# adapter.net
KiCad netlist of a schematic drawn in EAGLE
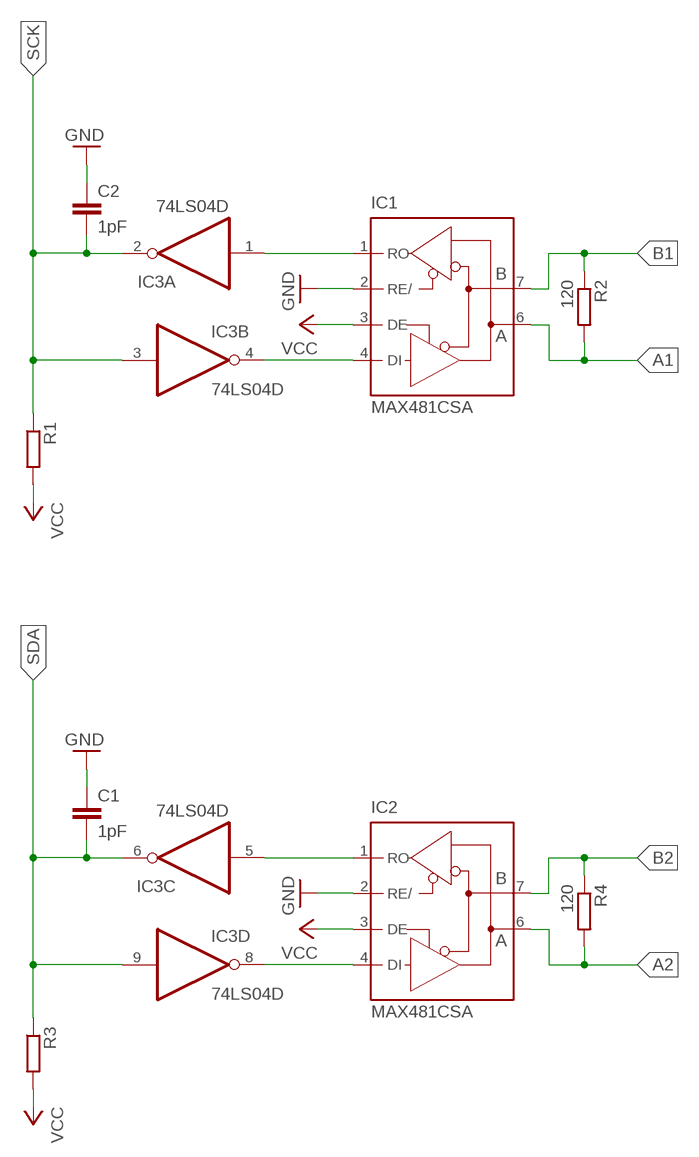
[diagram p0: schematic, sheet 1]

(export (version "E")
  (design (tool "Eeschema 10.0.6"))
  (components
    (comp (ref "C1")
      (value "1pF")
      (footprint "eagle-import:C0805")
      (libsource (lib "eagle-import") (part "C"))
    )
    (comp (ref "C2")
      (value "1pF")
      (footprint "eagle-import:C0805")
      (libsource (lib "eagle-import") (part "C"))
    )
    (comp (ref "IC1")
      (value "MAX481CSA")
      (footprint "eagle-import:SO08")
      (libsource (lib "eagle-import") (part "MAX481CSA"))
    )
    (comp (ref "IC2")
      (value "MAX481CSA")
      (footprint "eagle-import:SO08")
      (libsource (lib "eagle-import") (part "MAX481CSA"))
    )
    (comp (ref "IC3")
      (value "74LS04D")
      (footprint "eagle-import:SO14")
      (libsource (lib "eagle-import") (part "7404DLS"))
    )
    (comp (ref "R1")
      (value "R0204/7")
      (footprint "eagle-import:0204_7")
      (libsource (lib "eagle-import") (part "R0204/7"))
    )
    (comp (ref "R2")
      (value "120")
      (footprint "eagle-import:0204_7")
      (libsource (lib "eagle-import") (part "R0204/7"))
    )
    (comp (ref "R3")
      (value "R0204/7")
      (footprint "eagle-import:0204_7")
      (libsource (lib "eagle-import") (part "R0204/7"))
    )
    (comp (ref "R4")
      (value "120")
      (footprint "eagle-import:0204_7")
      (libsource (lib "eagle-import") (part "R0204/7"))
    )
  )
  (nets
    (net (code "1") (name "A1") (class "Default")
      (node (ref "IC1") (pin "6") (pinfunction "A_6") (pintype "passive"))
      (node (ref "R2") (pin "2") (pinfunction "2_2") (pintype "passive"))
    )
    (net (code "2") (name "A2") (class "Default")
      (node (ref "IC2") (pin "6") (pinfunction "A_6") (pintype "passive"))
      (node (ref "R4") (pin "2") (pinfunction "2_2") (pintype "passive"))
    )
    (net (code "3") (name "B1") (class "Default")
      (node (ref "IC1") (pin "7") (pinfunction "B_7") (pintype "passive"))
      (node (ref "R2") (pin "1") (pinfunction "1_1") (pintype "passive"))
    )
    (net (code "4") (name "B2") (class "Default")
      (node (ref "IC2") (pin "7") (pinfunction "B_7") (pintype "passive"))
      (node (ref "R4") (pin "1") (pinfunction "1_1") (pintype "passive"))
    )
    (net (code "5") (name "GND") (class "Default")
      (node (ref "C1") (pin "1") (pinfunction "1_1") (pintype "passive"))
      (node (ref "C2") (pin "1") (pinfunction "1_1") (pintype "passive"))
      (node (ref "IC1") (pin "2") (pinfunction "RE/_2") (pintype "input"))
      (node (ref "IC2") (pin "2") (pinfunction "RE/_2") (pintype "input"))
    )
    (net (code "6") (name "Net-(IC1A-DI)") (class "Default")
      (node (ref "IC1") (pin "4") (pinfunction "DI_4") (pintype "input"))
      (node (ref "IC3") (pin "4") (pinfunction "O_4") (pintype "output"))
    )
    (net (code "7") (name "Net-(IC1A-RO)") (class "Default")
      (node (ref "IC1") (pin "1") (pinfunction "RO_1") (pintype "output"))
      (node (ref "IC3") (pin "1") (pinfunction "I_1") (pintype "input"))
    )
    (net (code "8") (name "Net-(IC2A-DI)") (class "Default")
      (node (ref "IC2") (pin "4") (pinfunction "DI_4") (pintype "input"))
      (node (ref "IC3") (pin "8") (pinfunction "O_8") (pintype "output"))
    )
    (net (code "9") (name "Net-(IC2A-RO)") (class "Default")
      (node (ref "IC2") (pin "1") (pinfunction "RO_1") (pintype "output"))
      (node (ref "IC3") (pin "5") (pinfunction "I_5") (pintype "input"))
    )
    (net (code "10") (name "SCK") (class "Default")
      (node (ref "C2") (pin "2") (pinfunction "2_2") (pintype "passive"))
      (node (ref "IC3") (pin "2") (pinfunction "O_2") (pintype "output"))
      (node (ref "IC3") (pin "3") (pinfunction "I_3") (pintype "input"))
      (node (ref "R1") (pin "1") (pinfunction "1_1") (pintype "passive"))
    )
    (net (code "11") (name "SDA") (class "Default")
      (node (ref "C1") (pin "2") (pinfunction "2_2") (pintype "passive"))
      (node (ref "IC3") (pin "6") (pinfunction "O_6") (pintype "output"))
      (node (ref "IC3") (pin "9") (pinfunction "I_9") (pintype "input"))
      (node (ref "R3") (pin "1") (pinfunction "1_1") (pintype "passive"))
    )
    (net (code "12") (name "VCC") (class "Default")
      (node (ref "IC1") (pin "3") (pinfunction "DE_3") (pintype "input"))
      (node (ref "IC2") (pin "3") (pinfunction "DE_3") (pintype "input"))
      (node (ref "R1") (pin "2") (pinfunction "2_2") (pintype "passive"))
      (node (ref "R3") (pin "2") (pinfunction "2_2") (pintype "passive"))
    )
  )
)
